# Analog-Wall-Clock.net
KiCad netlist of a schematic drawn in EAGLE
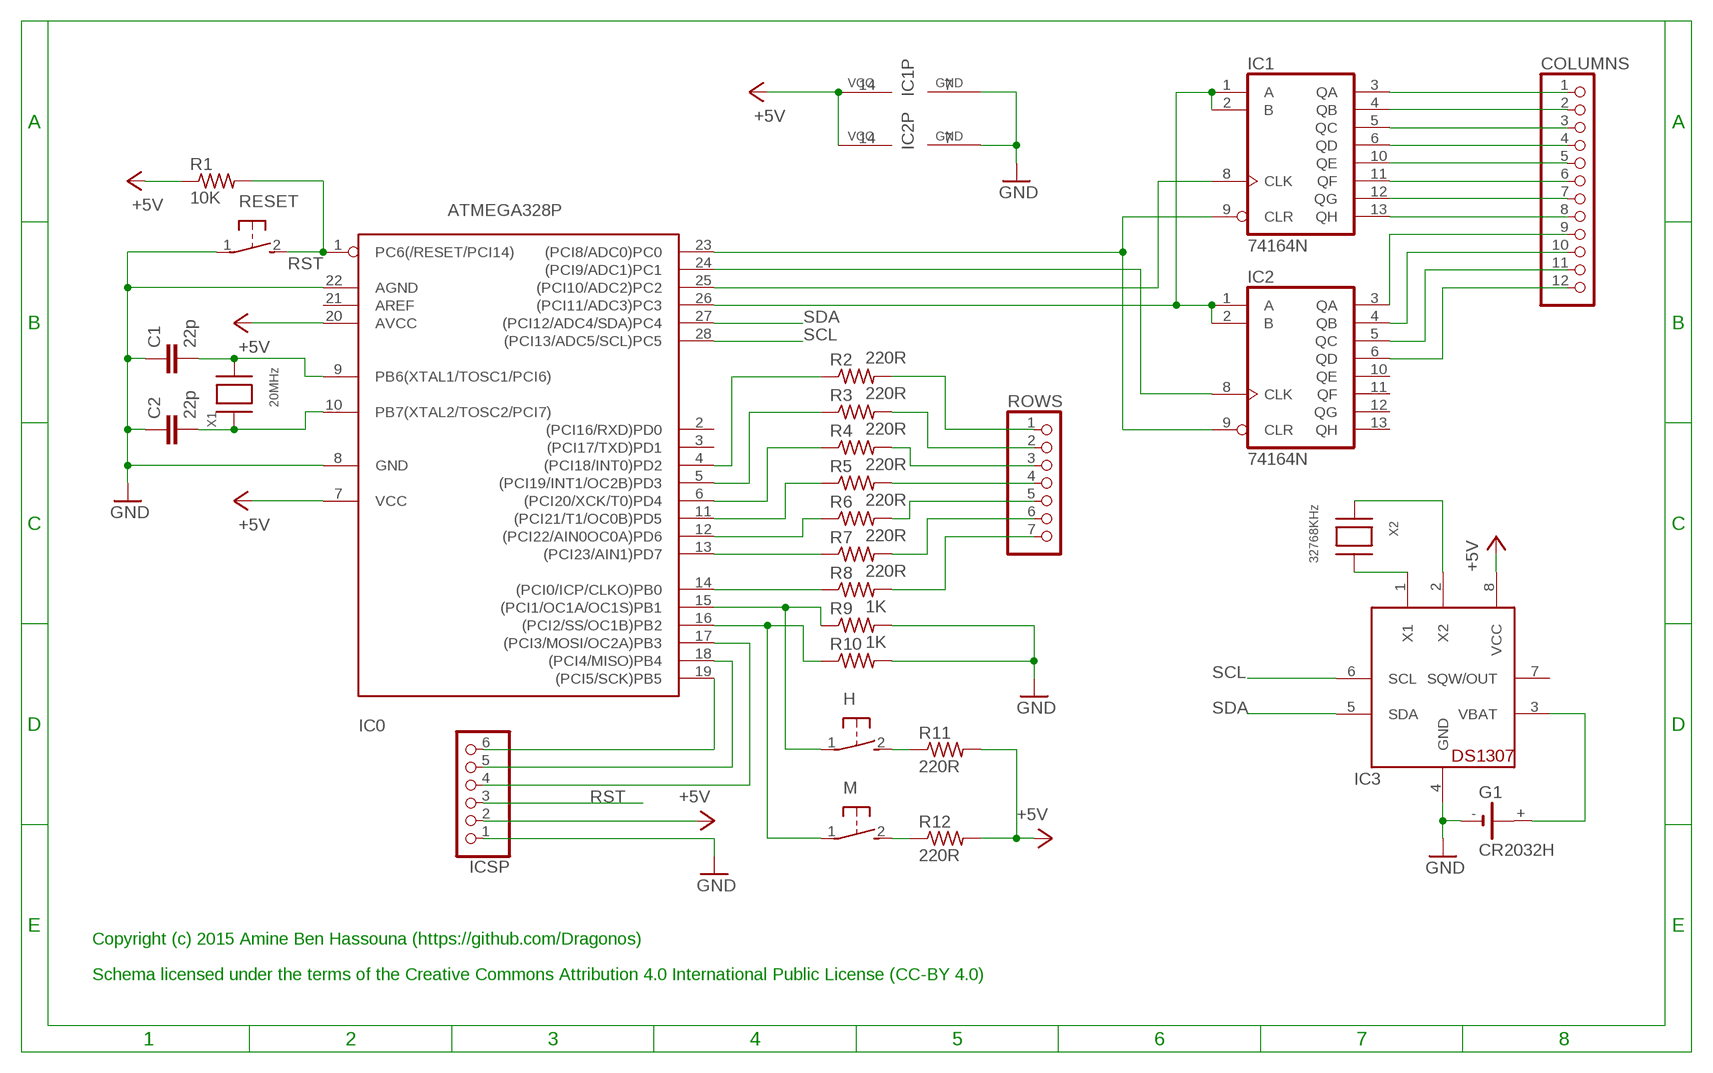
[diagram p0: schematic, sheet 1]

(export (version "E")
  (design (tool "Eeschema 10.0.6"))
  (components
    (comp (ref "C1")
      (value "22p")
      (footprint "eagle-import:C2.5-3")
      (libsource (lib "eagle-import") (part "C2,5-3"))
    )
    (comp (ref "C2")
      (value "22p")
      (footprint "eagle-import:C2.5-3")
      (libsource (lib "eagle-import") (part "C2,5-3"))
    )
    (comp (ref "COLUMNS")
      (value "PINHD-1X12")
      (footprint "eagle-import:1X12")
      (libsource (lib "eagle-import") (part "PINHD-1X12"))
    )
    (comp (ref "G1")
      (value "CR2032H")
      (footprint "eagle-import:CR2032H")
      (libsource (lib "eagle-import") (part "CR2032H"))
    )
    (comp (ref "H")
      (value "31-XX")
      (footprint "eagle-import:B3F-31XX")
      (fields (field (name "MPN") "B3F-3100"))
      (libsource (lib "eagle-import") (part "31-XX"))
    )
    (comp (ref "IC0")
      (value "ATMEGA328P")
      (footprint "eagle-import:DIL28-3")
      (libsource (lib "eagle-import") (part "ATMEGA168P-20"))
    )
    (comp (ref "IC1")
      (value "74164N")
      (footprint "eagle-import:DIL14")
      (libsource (lib "eagle-import") (part "74164N"))
    )
    (comp (ref "IC2")
      (value "74164N")
      (footprint "eagle-import:DIL14")
      (libsource (lib "eagle-import") (part "74164N"))
    )
    (comp (ref "IC3")
      (value "DS1307")
      (footprint "eagle-import:DIL08")
      (libsource (lib "eagle-import") (part "DS1307"))
    )
    (comp (ref "ICSP")
      (value "PINHD-1X6")
      (footprint "eagle-import:1X06")
      (libsource (lib "eagle-import") (part "PINHD-1X6"))
    )
    (comp (ref "M")
      (value "31-XX")
      (footprint "eagle-import:B3F-31XX")
      (fields (field (name "MPN") "B3F-3100"))
      (libsource (lib "eagle-import") (part "31-XX"))
    )
    (comp (ref "R1")
      (value "10K")
      (footprint "eagle-import:0207_10")
      (libsource (lib "eagle-import") (part "R-US_0207/10"))
    )
    (comp (ref "R2")
      (value "220R")
      (footprint "eagle-import:0207_10")
      (libsource (lib "eagle-import") (part "R-US_0207/10"))
    )
    (comp (ref "R3")
      (value "220R")
      (footprint "eagle-import:0207_10")
      (libsource (lib "eagle-import") (part "R-US_0207/10"))
    )
    (comp (ref "R4")
      (value "220R")
      (footprint "eagle-import:0207_10")
      (libsource (lib "eagle-import") (part "R-US_0207/10"))
    )
    (comp (ref "R5")
      (value "220R")
      (footprint "eagle-import:0207_10")
      (libsource (lib "eagle-import") (part "R-US_0207/10"))
    )
    (comp (ref "R6")
      (value "220R")
      (footprint "eagle-import:0207_10")
      (libsource (lib "eagle-import") (part "R-US_0207/10"))
    )
    (comp (ref "R7")
      (value "220R")
      (footprint "eagle-import:0207_10")
      (libsource (lib "eagle-import") (part "R-US_0207/10"))
    )
    (comp (ref "R8")
      (value "220R")
      (footprint "eagle-import:0207_10")
      (libsource (lib "eagle-import") (part "R-US_0207/10"))
    )
    (comp (ref "R9")
      (value "1K")
      (footprint "eagle-import:0207_10")
      (libsource (lib "eagle-import") (part "R-US_0207/10"))
    )
    (comp (ref "R10")
      (value "1K")
      (footprint "eagle-import:0207_10")
      (libsource (lib "eagle-import") (part "R-US_0207/10"))
    )
    (comp (ref "R11")
      (value "220R")
      (footprint "eagle-import:0207_10")
      (libsource (lib "eagle-import") (part "R-US_0207/10"))
    )
    (comp (ref "R12")
      (value "220R")
      (footprint "eagle-import:0207_10")
      (libsource (lib "eagle-import") (part "R-US_0207/10"))
    )
    (comp (ref "RESET")
      (value "31-XX")
      (footprint "eagle-import:B3F-31XX")
      (fields (field (name "MPN") "B3F-3100"))
      (libsource (lib "eagle-import") (part "31-XX"))
    )
    (comp (ref "ROWS")
      (value "PINHD-1X7")
      (footprint "eagle-import:1X07")
      (libsource (lib "eagle-import") (part "PINHD-1X7"))
    )
    (comp (ref "X1")
      (value "20MHz")
      (footprint "eagle-import:XTAL3215")
      (libsource (lib "eagle-import") (part "XTAL-3.2X1.5"))
    )
    (comp (ref "X2")
      (value "32768KHz")
      (footprint "eagle-import:XTAL3215")
      (libsource (lib "eagle-import") (part "XTAL-3.2X1.5"))
    )
  )
  (nets
    (net (code "1") (name "+5V") (class "Default")
      (node (ref "IC0") (pin "20") (pinfunction "AVCC_20") (pintype "bidirectional"))
      (node (ref "IC0") (pin "7") (pinfunction "VCC_7") (pintype "bidirectional"))
      (node (ref "IC1") (pin "14") (pinfunction "VCC_14") (pintype "power_in"))
      (node (ref "IC2") (pin "14") (pinfunction "VCC_14") (pintype "power_in"))
      (node (ref "IC3") (pin "8") (pinfunction "VCC_8") (pintype "power_in"))
      (node (ref "ICSP") (pin "2") (pinfunction "2_2") (pintype "passive"))
      (node (ref "R1") (pin "1") (pinfunction "1_1") (pintype "passive"))
      (node (ref "R11") (pin "2") (pinfunction "2_2") (pintype "passive"))
      (node (ref "R12") (pin "2") (pinfunction "2_2") (pintype "passive"))
    )
    (net (code "2") (name "/RST") (class "Default")
      (node (ref "IC0") (pin "1") (pinfunction "PC6(/RESET/PCI14)_1") (pintype "bidirectional"))
      (node (ref "ICSP") (pin "3") (pinfunction "3_3") (pintype "passive"))
      (node (ref "R1") (pin "2") (pinfunction "2_2") (pintype "passive"))
      (node (ref "RESET") (pin "2") (pinfunction "S_2") (pintype "passive"))
    )
    (net (code "3") (name "/SCL") (class "Default")
      (node (ref "IC0") (pin "28") (pinfunction "(PCI13/ADC5/SCL)PC5_28") (pintype "bidirectional"))
      (node (ref "IC3") (pin "6") (pinfunction "SCL_6") (pintype "bidirectional"))
    )
    (net (code "4") (name "/SDA") (class "Default")
      (node (ref "IC0") (pin "27") (pinfunction "(PCI12/ADC4/SDA)PC4_27") (pintype "bidirectional"))
      (node (ref "IC3") (pin "5") (pinfunction "SDA_5") (pintype "bidirectional"))
    )
    (net (code "5") (name "GND") (class "Default")
      (node (ref "C1") (pin "1") (pinfunction "1_1") (pintype "passive"))
      (node (ref "C2") (pin "1") (pinfunction "1_1") (pintype "passive"))
      (node (ref "G1") (pin "-") (pinfunction "-_-") (pintype "passive"))
      (node (ref "IC0") (pin "22") (pinfunction "AGND_22") (pintype "bidirectional"))
      (node (ref "IC0") (pin "8") (pinfunction "GND_8") (pintype "bidirectional"))
      (node (ref "IC1") (pin "7") (pinfunction "GND_7") (pintype "power_in"))
      (node (ref "IC2") (pin "7") (pinfunction "GND_7") (pintype "power_in"))
      (node (ref "IC3") (pin "4") (pinfunction "GND_4") (pintype "power_in"))
      (node (ref "ICSP") (pin "1") (pinfunction "1_1") (pintype "passive"))
      (node (ref "R10") (pin "2") (pinfunction "2_2") (pintype "passive"))
      (node (ref "R9") (pin "2") (pinfunction "2_2") (pintype "passive"))
      (node (ref "RESET") (pin "1") (pinfunction "P_1") (pintype "passive"))
    )
    (net (code "6") (name "Net-(H-P)") (class "Default")
      (node (ref "H") (pin "1") (pinfunction "P_1") (pintype "passive"))
      (node (ref "IC0") (pin "15") (pinfunction "(PCI1/OC1A/OC1S)PB1_15") (pintype "bidirectional"))
      (node (ref "R9") (pin "1") (pinfunction "1_1") (pintype "passive"))
    )
    (net (code "7") (name "Net-(H-S)") (class "Default")
      (node (ref "H") (pin "2") (pinfunction "S_2") (pintype "passive"))
      (node (ref "R11") (pin "1") (pinfunction "1_1") (pintype "passive"))
    )
    (net (code "8") (name "Net-(IC0-(PCI0{slash}ICP{slash}CLKO)PB0)") (class "Default")
      (node (ref "IC0") (pin "14") (pinfunction "(PCI0/ICP/CLKO)PB0_14") (pintype "bidirectional"))
      (node (ref "R8") (pin "1") (pinfunction "1_1") (pintype "passive"))
    )
    (net (code "9") (name "Net-(IC0-(PCI2{slash}SS{slash}OC1B)PB2)") (class "Default")
      (node (ref "IC0") (pin "16") (pinfunction "(PCI2/SS/OC1B)PB2_16") (pintype "bidirectional"))
      (node (ref "M") (pin "1") (pinfunction "P_1") (pintype "passive"))
      (node (ref "R10") (pin "1") (pinfunction "1_1") (pintype "passive"))
    )
    (net (code "10") (name "Net-(IC0-(PCI3{slash}MOSI{slash}OC2A)PB3)") (class "Default")
      (node (ref "IC0") (pin "17") (pinfunction "(PCI3/MOSI/OC2A)PB3_17") (pintype "bidirectional"))
      (node (ref "ICSP") (pin "4") (pinfunction "4_4") (pintype "passive"))
    )
    (net (code "11") (name "Net-(IC0-(PCI4{slash}MISO)PB4)") (class "Default")
      (node (ref "IC0") (pin "18") (pinfunction "(PCI4/MISO)PB4_18") (pintype "bidirectional"))
      (node (ref "ICSP") (pin "5") (pinfunction "5_5") (pintype "passive"))
    )
    (net (code "12") (name "Net-(IC0-(PCI5{slash}SCK)PB5)") (class "Default")
      (node (ref "IC0") (pin "19") (pinfunction "(PCI5/SCK)PB5_19") (pintype "bidirectional"))
      (node (ref "ICSP") (pin "6") (pinfunction "6_6") (pintype "passive"))
    )
    (net (code "13") (name "Net-(IC0-(PCI8{slash}ADC0)PC0)") (class "Default")
      (node (ref "IC0") (pin "23") (pinfunction "(PCI8/ADC0)PC0_23") (pintype "bidirectional"))
      (node (ref "IC1") (pin "9") (pinfunction "CLR_9") (pintype "input"))
      (node (ref "IC2") (pin "9") (pinfunction "CLR_9") (pintype "input"))
    )
    (net (code "14") (name "Net-(IC0-(PCI9{slash}ADC1)PC1)") (class "Default")
      (node (ref "IC0") (pin "24") (pinfunction "(PCI9/ADC1)PC1_24") (pintype "bidirectional"))
      (node (ref "IC2") (pin "8") (pinfunction "CLK_8") (pintype "input"))
    )
    (net (code "15") (name "Net-(IC0-(PCI10{slash}ADC2)PC2)") (class "Default")
      (node (ref "IC0") (pin "25") (pinfunction "(PCI10/ADC2)PC2_25") (pintype "bidirectional"))
      (node (ref "IC1") (pin "8") (pinfunction "CLK_8") (pintype "input"))
    )
    (net (code "16") (name "Net-(IC0-(PCI11{slash}ADC3)PC3)") (class "Default")
      (node (ref "IC0") (pin "26") (pinfunction "(PCI11/ADC3)PC3_26") (pintype "bidirectional"))
      (node (ref "IC1") (pin "1") (pinfunction "A_1") (pintype "input"))
      (node (ref "IC1") (pin "2") (pinfunction "B_2") (pintype "input"))
      (node (ref "IC2") (pin "1") (pinfunction "A_1") (pintype "input"))
      (node (ref "IC2") (pin "2") (pinfunction "B_2") (pintype "input"))
    )
    (net (code "17") (name "Net-(IC0-(PCI18{slash}INT0)PD2)") (class "Default")
      (node (ref "IC0") (pin "4") (pinfunction "(PCI18/INT0)PD2_4") (pintype "bidirectional"))
      (node (ref "R2") (pin "1") (pinfunction "1_1") (pintype "passive"))
    )
    (net (code "18") (name "Net-(IC0-(PCI19{slash}INT1{slash}OC2B)PD3)") (class "Default")
      (node (ref "IC0") (pin "5") (pinfunction "(PCI19/INT1/OC2B)PD3_5") (pintype "bidirectional"))
      (node (ref "R3") (pin "1") (pinfunction "1_1") (pintype "passive"))
    )
    (net (code "19") (name "Net-(IC0-(PCI20{slash}XCK{slash}T0)PD4)") (class "Default")
      (node (ref "IC0") (pin "6") (pinfunction "(PCI20/XCK/T0)PD4_6") (pintype "bidirectional"))
      (node (ref "R4") (pin "1") (pinfunction "1_1") (pintype "passive"))
    )
    (net (code "20") (name "Net-(IC0-(PCI21{slash}T1{slash}OC0B)PD5)") (class "Default")
      (node (ref "IC0") (pin "11") (pinfunction "(PCI21/T1/OC0B)PD5_11") (pintype "bidirectional"))
      (node (ref "R5") (pin "1") (pinfunction "1_1") (pintype "passive"))
    )
    (net (code "21") (name "Net-(IC0-(PCI22{slash}AIN0OC0A)PD6)") (class "Default")
      (node (ref "IC0") (pin "12") (pinfunction "(PCI22/AIN0OC0A)PD6_12") (pintype "bidirectional"))
      (node (ref "R6") (pin "1") (pinfunction "1_1") (pintype "passive"))
    )
    (net (code "22") (name "Net-(IC0-(PCI23{slash}AIN1)PD7)") (class "Default")
      (node (ref "IC0") (pin "13") (pinfunction "(PCI23/AIN1)PD7_13") (pintype "bidirectional"))
      (node (ref "R7") (pin "1") (pinfunction "1_1") (pintype "passive"))
    )
    (net (code "23") (name "Net-(IC0-PB6(XTAL1{slash}TOSC1{slash}PCI6))") (class "Default")
      (node (ref "C1") (pin "2") (pinfunction "2_2") (pintype "passive"))
      (node (ref "IC0") (pin "9") (pinfunction "PB6(XTAL1/TOSC1/PCI6)_9") (pintype "bidirectional"))
      (node (ref "X1") (pin "P$1") (pinfunction "P$1_P$1") (pintype "bidirectional"))
    )
    (net (code "24") (name "Net-(IC0-PB7(XTAL2{slash}TOSC2{slash}PCI7))") (class "Default")
      (node (ref "C2") (pin "2") (pinfunction "2_2") (pintype "passive"))
      (node (ref "IC0") (pin "10") (pinfunction "PB7(XTAL2/TOSC2/PCI7)_10") (pintype "bidirectional"))
      (node (ref "X1") (pin "P$2") (pinfunction "P$2_P$2") (pintype "bidirectional"))
    )
    (net (code "25") (name "Net-(IC1A-QA)") (class "Default")
      (node (ref "COLUMNS") (pin "1") (pinfunction "1_1") (pintype "passive"))
      (node (ref "IC1") (pin "3") (pinfunction "QA_3") (pintype "output"))
    )
    (net (code "26") (name "Net-(IC1A-QB)") (class "Default")
      (node (ref "COLUMNS") (pin "2") (pinfunction "2_2") (pintype "passive"))
      (node (ref "IC1") (pin "4") (pinfunction "QB_4") (pintype "output"))
    )
    (net (code "27") (name "Net-(IC1A-QC)") (class "Default")
      (node (ref "COLUMNS") (pin "3") (pinfunction "3_3") (pintype "passive"))
      (node (ref "IC1") (pin "5") (pinfunction "QC_5") (pintype "output"))
    )
    (net (code "28") (name "Net-(IC1A-QD)") (class "Default")
      (node (ref "COLUMNS") (pin "4") (pinfunction "4_4") (pintype "passive"))
      (node (ref "IC1") (pin "6") (pinfunction "QD_6") (pintype "output"))
    )
    (net (code "29") (name "Net-(IC1A-QE)") (class "Default")
      (node (ref "COLUMNS") (pin "5") (pinfunction "5_5") (pintype "passive"))
      (node (ref "IC1") (pin "10") (pinfunction "QE_10") (pintype "output"))
    )
    (net (code "30") (name "Net-(IC1A-QF)") (class "Default")
      (node (ref "COLUMNS") (pin "6") (pinfunction "6_6") (pintype "passive"))
      (node (ref "IC1") (pin "11") (pinfunction "QF_11") (pintype "output"))
    )
    (net (code "31") (name "Net-(IC1A-QG)") (class "Default")
      (node (ref "COLUMNS") (pin "7") (pinfunction "7_7") (pintype "passive"))
      (node (ref "IC1") (pin "12") (pinfunction "QG_12") (pintype "output"))
    )
    (net (code "32") (name "Net-(IC1A-QH)") (class "Default")
      (node (ref "COLUMNS") (pin "8") (pinfunction "8_8") (pintype "passive"))
      (node (ref "IC1") (pin "13") (pinfunction "QH_13") (pintype "output"))
    )
    (net (code "33") (name "Net-(IC2A-QA)") (class "Default")
      (node (ref "COLUMNS") (pin "9") (pinfunction "9_9") (pintype "passive"))
      (node (ref "IC2") (pin "3") (pinfunction "QA_3") (pintype "output"))
    )
    (net (code "34") (name "Net-(IC2A-QB)") (class "Default")
      (node (ref "COLUMNS") (pin "10") (pinfunction "10_10") (pintype "passive"))
      (node (ref "IC2") (pin "4") (pinfunction "QB_4") (pintype "output"))
    )
    (net (code "35") (name "Net-(IC2A-QC)") (class "Default")
      (node (ref "COLUMNS") (pin "11") (pinfunction "11_11") (pintype "passive"))
      (node (ref "IC2") (pin "5") (pinfunction "QC_5") (pintype "output"))
    )
    (net (code "36") (name "Net-(IC2A-QD)") (class "Default")
      (node (ref "COLUMNS") (pin "12") (pinfunction "12_12") (pintype "passive"))
      (node (ref "IC2") (pin "6") (pinfunction "QD_6") (pintype "output"))
    )
    (net (code "37") (name "Net-(IC3-VBAT)") (class "Default")
      (node (ref "G1") (pin "+") (pinfunction "+_+") (pintype "passive"))
      (node (ref "IC3") (pin "3") (pinfunction "VBAT_3") (pintype "power_in"))
    )
    (net (code "38") (name "Net-(IC3-X1)") (class "Default")
      (node (ref "IC3") (pin "1") (pinfunction "X1_1") (pintype "passive"))
      (node (ref "X2") (pin "P$1") (pinfunction "P$1_P$1") (pintype "bidirectional"))
    )
    (net (code "39") (name "Net-(IC3-X2)") (class "Default")
      (node (ref "IC3") (pin "2") (pinfunction "X2_2") (pintype "passive"))
      (node (ref "X2") (pin "P$2") (pinfunction "P$2_P$2") (pintype "bidirectional"))
    )
    (net (code "40") (name "Net-(M-S)") (class "Default")
      (node (ref "M") (pin "2") (pinfunction "S_2") (pintype "passive"))
      (node (ref "R12") (pin "1") (pinfunction "1_1") (pintype "passive"))
    )
    (net (code "41") (name "Net-(R2-Pad2)") (class "Default")
      (node (ref "R2") (pin "2") (pinfunction "2_2") (pintype "passive"))
      (node (ref "ROWS") (pin "1") (pinfunction "1_1") (pintype "passive"))
    )
    (net (code "42") (name "Net-(R3-Pad2)") (class "Default")
      (node (ref "R3") (pin "2") (pinfunction "2_2") (pintype "passive"))
      (node (ref "ROWS") (pin "2") (pinfunction "2_2") (pintype "passive"))
    )
    (net (code "43") (name "Net-(R4-Pad2)") (class "Default")
      (node (ref "R4") (pin "2") (pinfunction "2_2") (pintype "passive"))
      (node (ref "ROWS") (pin "3") (pinfunction "3_3") (pintype "passive"))
    )
    (net (code "44") (name "Net-(R5-Pad2)") (class "Default")
      (node (ref "R5") (pin "2") (pinfunction "2_2") (pintype "passive"))
      (node (ref "ROWS") (pin "4") (pinfunction "4_4") (pintype "passive"))
    )
    (net (code "45") (name "Net-(R6-Pad2)") (class "Default")
      (node (ref "R6") (pin "2") (pinfunction "2_2") (pintype "passive"))
      (node (ref "ROWS") (pin "5") (pinfunction "5_5") (pintype "passive"))
    )
    (net (code "46") (name "Net-(R7-Pad2)") (class "Default")
      (node (ref "R7") (pin "2") (pinfunction "2_2") (pintype "passive"))
      (node (ref "ROWS") (pin "6") (pinfunction "6_6") (pintype "passive"))
    )
    (net (code "47") (name "Net-(R8-Pad2)") (class "Default")
      (node (ref "R8") (pin "2") (pinfunction "2_2") (pintype "passive"))
      (node (ref "ROWS") (pin "7") (pinfunction "7_7") (pintype "passive"))
    )
    (net (code "48") (name "unconnected-(G1-+-Pad+@1)") (class "Default")
      (node (ref "G1") (pin "+@1") (pinfunction "+_+@1") (pintype "passive"))
    )
    (net (code "49") (name "unconnected-(IC0-(PCI16{slash}RXD)PD0-Pad2)") (class "Default")
      (node (ref "IC0") (pin "2") (pinfunction "(PCI16/RXD)PD0_2") (pintype "bidirectional"))
    )
    (net (code "50") (name "unconnected-(IC0-(PCI17{slash}TXD)PD1-Pad3)") (class "Default")
      (node (ref "IC0") (pin "3") (pinfunction "(PCI17/TXD)PD1_3") (pintype "bidirectional"))
    )
    (net (code "51") (name "unconnected-(IC0-AREF-Pad21)") (class "Default")
      (node (ref "IC0") (pin "21") (pinfunction "AREF_21") (pintype "bidirectional"))
    )
    (net (code "52") (name "unconnected-(IC2A-QE-Pad10)") (class "Default")
      (node (ref "IC2") (pin "10") (pinfunction "QE_10") (pintype "output"))
    )
    (net (code "53") (name "unconnected-(IC2A-QF-Pad11)") (class "Default")
      (node (ref "IC2") (pin "11") (pinfunction "QF_11") (pintype "output"))
    )
    (net (code "54") (name "unconnected-(IC2A-QG-Pad12)") (class "Default")
      (node (ref "IC2") (pin "12") (pinfunction "QG_12") (pintype "output"))
    )
    (net (code "55") (name "unconnected-(IC2A-QH-Pad13)") (class "Default")
      (node (ref "IC2") (pin "13") (pinfunction "QH_13") (pintype "output"))
    )
    (net (code "56") (name "unconnected-(IC3-SQW{slash}OUT-Pad7)") (class "Default")
      (node (ref "IC3") (pin "7") (pinfunction "SQW/OUT_7") (pintype "bidirectional"))
    )
  )
)
